# F3-Octo-Brushed-SIDE-USB.net
KiCad netlist of a schematic drawn in EAGLE
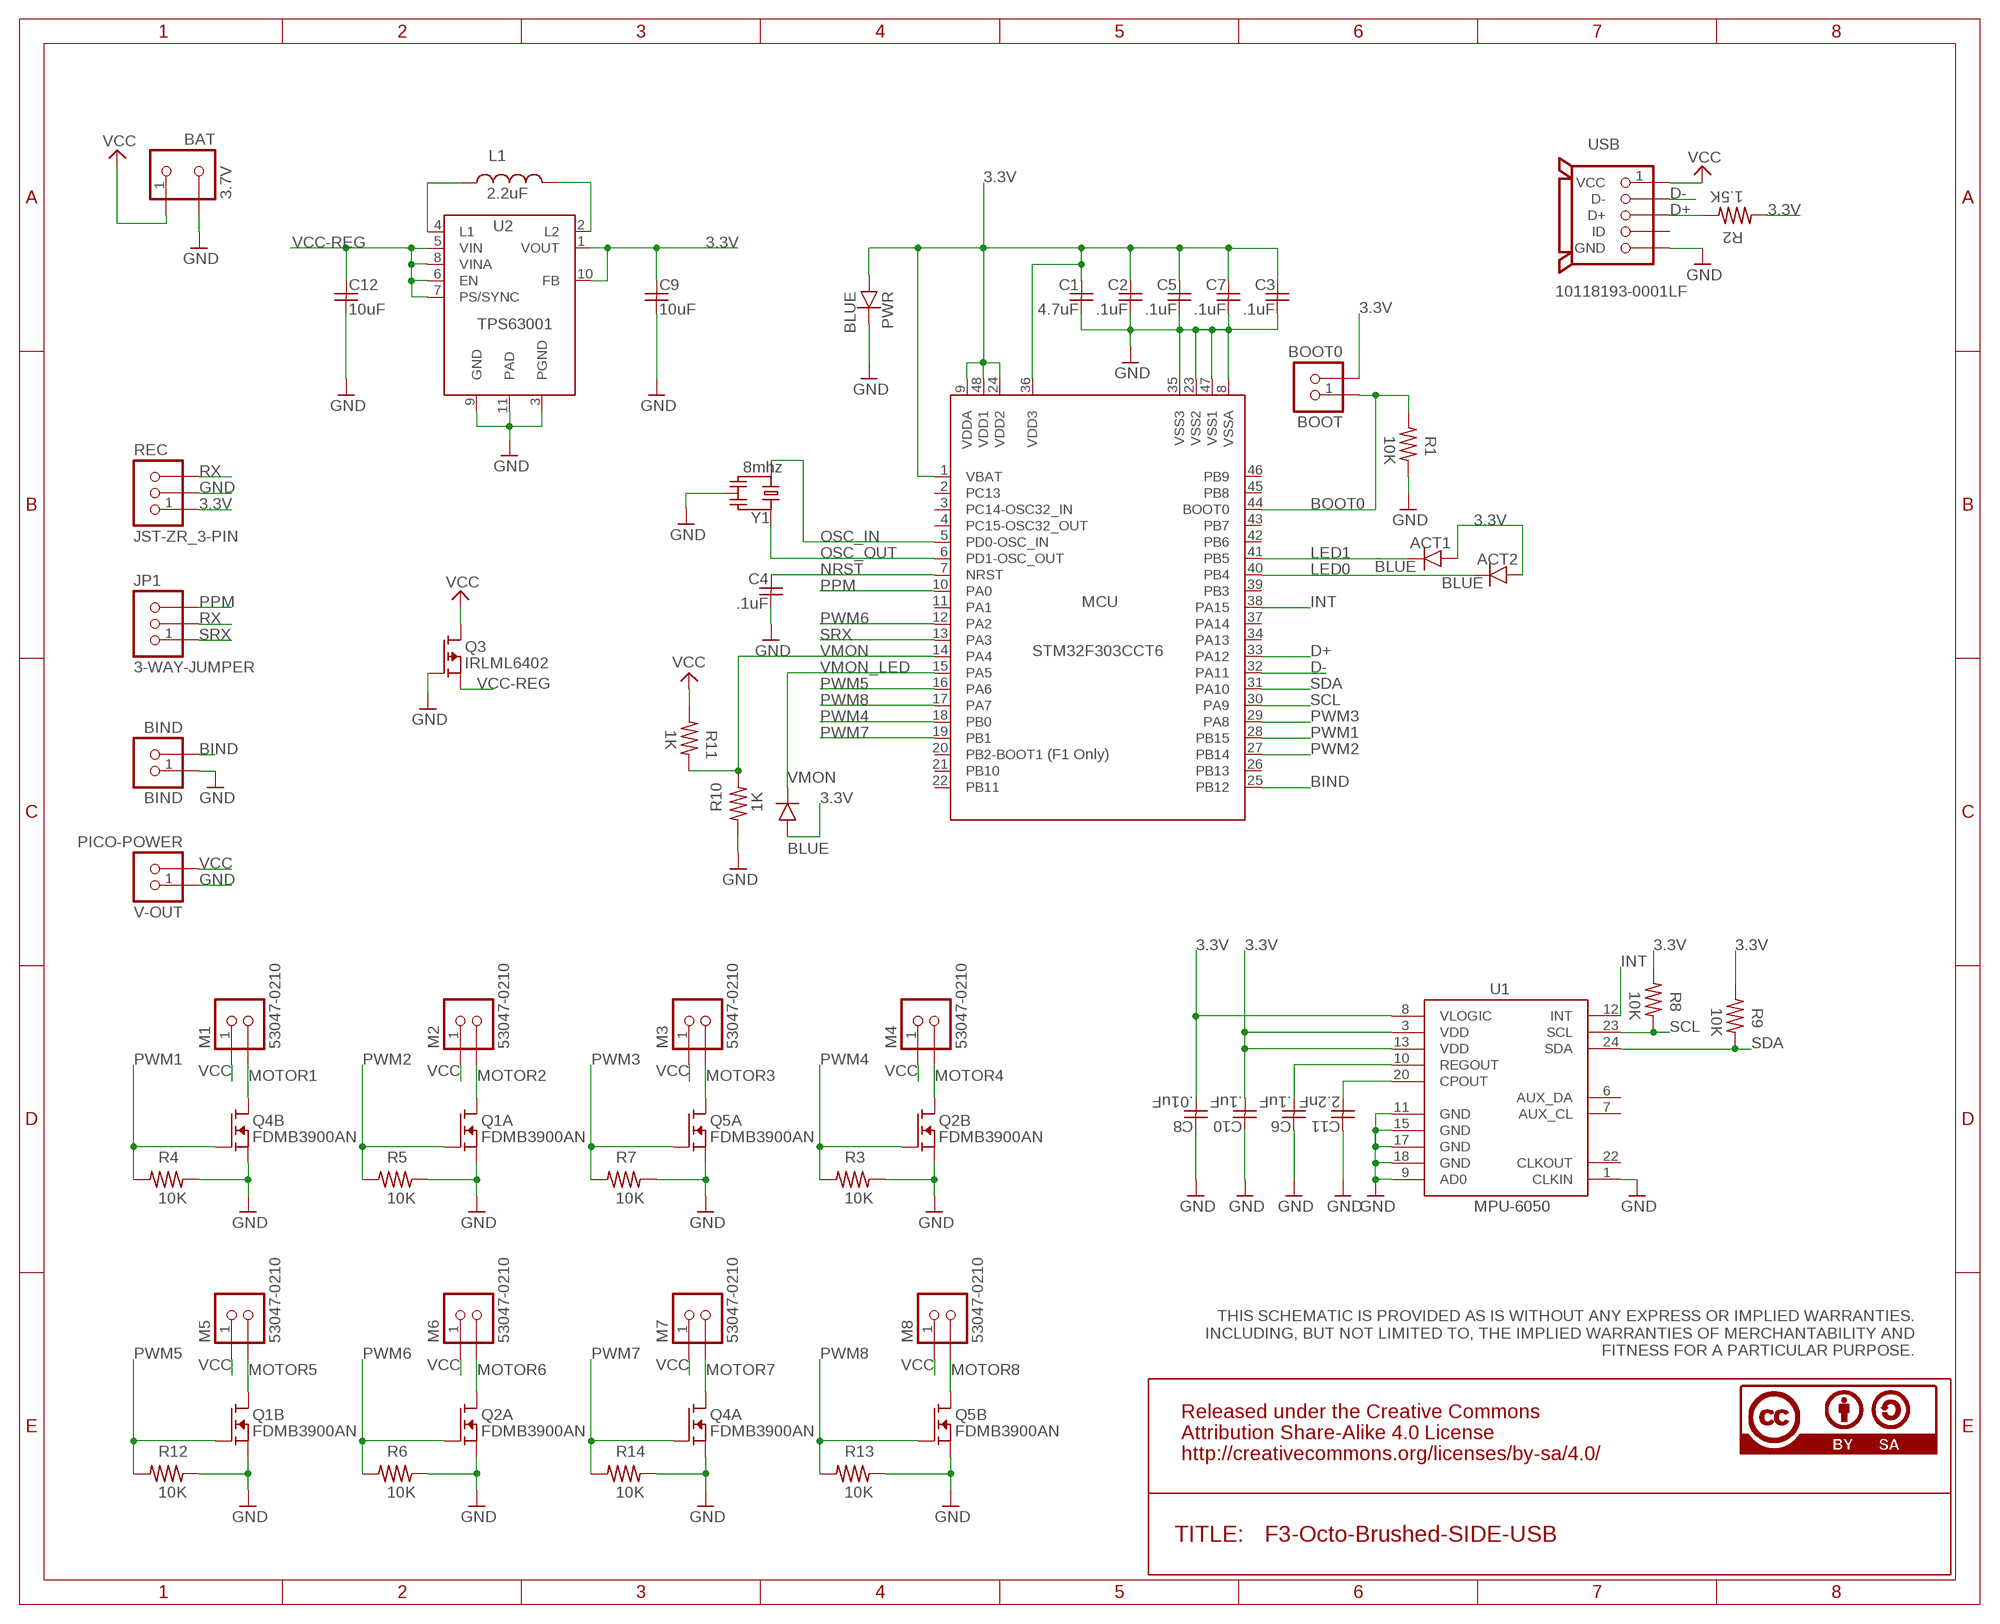
[diagram p0: schematic, sheet 1]

(export (version "E")
  (design (tool "Eeschema 10.0.6"))
  (components
    (comp (ref "ACT1")
      (value "BLUE")
      (footprint "eagle-import:SMD-CHIP-LED-0805")
      (fields (field (name "MF") "Kingbright") (field (name "MPN") "APHCM2012QBC/D-F01"))
      (libsource (lib "eagle-import") (part "SMD-CHIP-LED-0805"))
    )
    (comp (ref "ACT2")
      (value "BLUE")
      (footprint "eagle-import:SMD-CHIP-LED-0805")
      (fields (field (name "MF") "Kingbright") (field (name "MPN") "APHCM2012QBC/D-F01"))
      (libsource (lib "eagle-import") (part "SMD-CHIP-LED-0805"))
    )
    (comp (ref "BAT")
      (value "3.7V")
      (footprint "eagle-import:S2B-PH-K-S")
      (fields (field (name "MF") "JST") (field (name "MPN") "S2B-PH-K-S"))
      (libsource (lib "eagle-import") (part "JST-PH-BAT"))
    )
    (comp (ref "BIND")
      (value "BIND")
      (footprint "eagle-import:B3U-1000P(M)")
      (fields (field (name "MF") "Omron") (field (name "MPN") "B3U-1000P"))
      (libsource (lib "eagle-import") (part "TACTILE-SWITCH"))
    )
    (comp (ref "BOOT")
      (value "BOOT0")
      (footprint "eagle-import:B3U-1000P(M)")
      (fields (field (name "MF") "Omron") (field (name "MPN") "B3U-1000P"))
      (libsource (lib "eagle-import") (part "TACTILE-SWITCH"))
    )
    (comp (ref "C1")
      (value "4.7uF")
      (footprint "eagle-import:MUR-CAP-0603")
      (fields (field (name "MF") "Murata") (field (name "MPN") "GRJ188C70J475KE11D"))
      (libsource (lib "eagle-import") (part "CAPACITOR4.7UF"))
    )
    (comp (ref "C2")
      (value ".1uF")
      (footprint "eagle-import:MUR-CAP-0603")
      (fields (field (name "MF") "Murata") (field (name "MPN") "GRM188R71C104KA01D"))
      (libsource (lib "eagle-import") (part "CAPACITOR.1UF"))
    )
    (comp (ref "C3")
      (value ".1uF")
      (footprint "eagle-import:MUR-CAP-0603")
      (fields (field (name "MF") "Murata") (field (name "MPN") "GRM188R71C104KA01D"))
      (libsource (lib "eagle-import") (part "CAPACITOR.1UF"))
    )
    (comp (ref "C4")
      (value ".1uF")
      (footprint "eagle-import:MUR-CAP-0603")
      (fields (field (name "MF") "Murata") (field (name "MPN") "GRM188R71C104KA01D"))
      (libsource (lib "eagle-import") (part "CAPACITOR.1UF"))
    )
    (comp (ref "C5")
      (value ".1uF")
      (footprint "eagle-import:MUR-CAP-0603")
      (fields (field (name "MF") "Murata") (field (name "MPN") "GRM188R71C104KA01D"))
      (libsource (lib "eagle-import") (part "CAPACITOR.1UF"))
    )
    (comp (ref "C6")
      (value ".1uF")
      (footprint "eagle-import:MUR-CAP-0603")
      (fields (field (name "MF") "Murata") (field (name "MPN") "GRM188R71C104KA01D"))
      (libsource (lib "eagle-import") (part "CAPACITOR.1UF"))
    )
    (comp (ref "C7")
      (value ".1uF")
      (footprint "eagle-import:MUR-CAP-0603")
      (fields (field (name "MF") "Murata") (field (name "MPN") "GRM188R71C104KA01D"))
      (libsource (lib "eagle-import") (part "CAPACITOR.1UF"))
    )
    (comp (ref "C8")
      (value ".01uF")
      (footprint "eagle-import:MUR-CAP-0603")
      (fields (field (name "MF") "Murata") (field (name "MPN") "GRM188R71C103KA01D"))
      (libsource (lib "eagle-import") (part "CAPACITOR.01UF"))
    )
    (comp (ref "C9")
      (value "10uF")
      (footprint "eagle-import:YUDEN-CAP-0805")
      (fields (field (name "MF") "Taiyo Yuden") (field (name "MPN") "JMK212AB7106KG-T"))
      (libsource (lib "eagle-import") (part "CAPACITOR10UF"))
    )
    (comp (ref "C10")
      (value ".1uF")
      (footprint "eagle-import:MUR-CAP-0603")
      (fields (field (name "MF") "Murata") (field (name "MPN") "GRM188R71C104KA01D"))
      (libsource (lib "eagle-import") (part "CAPACITOR.1UF"))
    )
    (comp (ref "C11")
      (value "2.2nF")
      (footprint "eagle-import:MUR-CAP-0603")
      (fields (field (name "MF") "Murata") (field (name "MPN") "GRM188R71C222KA01D"))
      (libsource (lib "eagle-import") (part "CAPACITOR2.2NF"))
    )
    (comp (ref "C12")
      (value "10uF")
      (footprint "eagle-import:YUDEN-CAP-0805")
      (fields (field (name "MF") "Taiyo Yuden") (field (name "MPN") "JMK212AB7106KG-T"))
      (libsource (lib "eagle-import") (part "CAPACITOR10UF"))
    )
    (comp (ref "JP1")
      (value "3-WAY-JUMPER")
      (footprint "eagle-import:3-WAY-JUMPER")
      (libsource (lib "eagle-import") (part "3-WAY-JUMPER"))
    )
    (comp (ref "L1")
      (value "2.2uF")
      (footprint "eagle-import:NR301X")
      (fields (field (name "MF") "Taiyo Yuden") (field (name "MPN") "NR3015T2R2M"))
      (libsource (lib "eagle-import") (part "NR301X"))
    )
    (comp (ref "M1")
      (value "53047-0210")
      (footprint "eagle-import:PICO-53047-02")
      (fields (field (name "MF") "MOLEX"))
      (libsource (lib "eagle-import") (part "PICO-1.25-MOTOR"))
    )
    (comp (ref "M2")
      (value "53047-0210")
      (footprint "eagle-import:PICO-53047-02")
      (fields (field (name "MF") "MOLEX"))
      (libsource (lib "eagle-import") (part "PICO-1.25-MOTOR"))
    )
    (comp (ref "M3")
      (value "53047-0210")
      (footprint "eagle-import:PICO-53047-02")
      (fields (field (name "MF") "MOLEX"))
      (libsource (lib "eagle-import") (part "PICO-1.25-MOTOR"))
    )
    (comp (ref "M4")
      (value "53047-0210")
      (footprint "eagle-import:PICO-53047-02")
      (fields (field (name "MF") "MOLEX"))
      (libsource (lib "eagle-import") (part "PICO-1.25-MOTOR"))
    )
    (comp (ref "M5")
      (value "53047-0210")
      (footprint "eagle-import:PICO-53047-02")
      (fields (field (name "MF") "MOLEX"))
      (libsource (lib "eagle-import") (part "PICO-1.25-MOTOR"))
    )
    (comp (ref "M6")
      (value "53047-0210")
      (footprint "eagle-import:PICO-53047-02")
      (fields (field (name "MF") "MOLEX"))
      (libsource (lib "eagle-import") (part "PICO-1.25-MOTOR"))
    )
    (comp (ref "M7")
      (value "53047-0210")
      (footprint "eagle-import:PICO-53047-02")
      (fields (field (name "MF") "MOLEX"))
      (libsource (lib "eagle-import") (part "PICO-1.25-MOTOR"))
    )
    (comp (ref "M8")
      (value "53047-0210")
      (footprint "eagle-import:PICO-53047-02")
      (fields (field (name "MF") "MOLEX"))
      (libsource (lib "eagle-import") (part "PICO-1.25-MOTOR"))
    )
    (comp (ref "MCU")
      (value "STM32F303CCT6")
      (footprint "eagle-import:LQFP48-7X7")
      (fields (field (name "MF") "ST"))
      (libsource (lib "eagle-import") (part "STM32FX03-F3"))
    )
    (comp (ref "PWR")
      (value "BLUE")
      (footprint "eagle-import:SMD-CHIP-LED-0805")
      (fields (field (name "MF") "Kingbright") (field (name "MPN") "APHCM2012QBC/D-F01"))
      (libsource (lib "eagle-import") (part "SMD-CHIP-LED-0805"))
    )
    (comp (ref "Q1")
      (value "FDMB3900AN")
      (footprint "eagle-import:8-WDFN-DUAL")
      (fields (field (name "MF") "Fairchild"))
      (libsource (lib "eagle-import") (part "FDMB3900AN"))
    )
    (comp (ref "Q2")
      (value "FDMB3900AN")
      (footprint "eagle-import:8-WDFN-DUAL")
      (fields (field (name "MF") "Fairchild"))
      (libsource (lib "eagle-import") (part "FDMB3900AN"))
    )
    (comp (ref "Q3")
      (value "IRLML6402")
      (footprint "eagle-import:SOT-23")
      (fields (field (name "MF") "IR"))
      (libsource (lib "eagle-import") (part "IRLML6402"))
    )
    (comp (ref "Q4")
      (value "FDMB3900AN")
      (footprint "eagle-import:8-WDFN-DUAL")
      (fields (field (name "MF") "Fairchild"))
      (libsource (lib "eagle-import") (part "FDMB3900AN"))
    )
    (comp (ref "Q5")
      (value "FDMB3900AN")
      (footprint "eagle-import:8-WDFN-DUAL")
      (fields (field (name "MF") "Fairchild"))
      (libsource (lib "eagle-import") (part "FDMB3900AN"))
    )
    (comp (ref "R1")
      (value "10K")
      (footprint "eagle-import:VISH-RES-0603")
      (fields (field (name "MF") "Vishay") (field (name "MPN") "CRCW060310K0FKEAHP"))
      (libsource (lib "eagle-import") (part "RESISTOR10K"))
    )
    (comp (ref "R2")
      (value "1.5K")
      (footprint "eagle-import:VISH-RES-0603")
      (fields (field (name "MF") "Vishay") (field (name "MPN") "CRCW06031K50FKEAHP"))
      (libsource (lib "eagle-import") (part "RESISTOR1.5K"))
    )
    (comp (ref "R3")
      (value "10K")
      (footprint "eagle-import:VISH-RES-0603")
      (fields (field (name "MF") "Vishay") (field (name "MPN") "CRCW060310K0FKEAHP"))
      (libsource (lib "eagle-import") (part "RESISTOR10K"))
    )
    (comp (ref "R4")
      (value "10K")
      (footprint "eagle-import:VISH-RES-0603")
      (fields (field (name "MF") "Vishay") (field (name "MPN") "CRCW060310K0FKEAHP"))
      (libsource (lib "eagle-import") (part "RESISTOR10K"))
    )
    (comp (ref "R5")
      (value "10K")
      (footprint "eagle-import:VISH-RES-0603")
      (fields (field (name "MF") "Vishay") (field (name "MPN") "CRCW060310K0FKEAHP"))
      (libsource (lib "eagle-import") (part "RESISTOR10K"))
    )
    (comp (ref "R6")
      (value "10K")
      (footprint "eagle-import:VISH-RES-0603")
      (fields (field (name "MF") "Vishay") (field (name "MPN") "CRCW060310K0FKEAHP"))
      (libsource (lib "eagle-import") (part "RESISTOR10K"))
    )
    (comp (ref "R7")
      (value "10K")
      (footprint "eagle-import:VISH-RES-0603")
      (fields (field (name "MF") "Vishay") (field (name "MPN") "CRCW060310K0FKEAHP"))
      (libsource (lib "eagle-import") (part "RESISTOR10K"))
    )
    (comp (ref "R8")
      (value "10K")
      (footprint "eagle-import:VISH-RES-0603")
      (fields (field (name "MF") "Vishay") (field (name "MPN") "CRCW060310K0FKEAHP"))
      (libsource (lib "eagle-import") (part "RESISTOR10K"))
    )
    (comp (ref "R9")
      (value "10K")
      (footprint "eagle-import:VISH-RES-0603")
      (fields (field (name "MF") "Vishay") (field (name "MPN") "CRCW060310K0FKEAHP"))
      (libsource (lib "eagle-import") (part "RESISTOR10K"))
    )
    (comp (ref "R10")
      (value "1K")
      (footprint "eagle-import:VISH-RES-0603")
      (fields (field (name "MF") "Vishay") (field (name "MPN") "CRCW06031K00FKEAHP"))
      (libsource (lib "eagle-import") (part "RESISTOR1K"))
    )
    (comp (ref "R11")
      (value "1K")
      (footprint "eagle-import:VISH-RES-0603")
      (fields (field (name "MF") "Vishay") (field (name "MPN") "CRCW06031K00FKEAHP"))
      (libsource (lib "eagle-import") (part "RESISTOR1K"))
    )
    (comp (ref "R12")
      (value "10K")
      (footprint "eagle-import:VISH-RES-0603")
      (fields (field (name "MF") "Vishay") (field (name "MPN") "CRCW060310K0FKEAHP"))
      (libsource (lib "eagle-import") (part "RESISTOR10K"))
    )
    (comp (ref "R13")
      (value "10K")
      (footprint "eagle-import:VISH-RES-0603")
      (fields (field (name "MF") "Vishay") (field (name "MPN") "CRCW060310K0FKEAHP"))
      (libsource (lib "eagle-import") (part "RESISTOR10K"))
    )
    (comp (ref "R14")
      (value "10K")
      (footprint "eagle-import:VISH-RES-0603")
      (fields (field (name "MF") "Vishay") (field (name "MPN") "CRCW060310K0FKEAHP"))
      (libsource (lib "eagle-import") (part "RESISTOR10K"))
    )
    (comp (ref "REC")
      (value "JST-ZR_3-PIN")
      (footprint "eagle-import:S3B-ZR")
      (fields (field (name "MF") "JST") (field (name "MPN") "S3B-ZR"))
      (libsource (lib "eagle-import") (part "JST-ZR_3-PIN"))
    )
    (comp (ref "U1")
      (value "MPU-6050")
      (footprint "eagle-import:QFN24-4X4")
      (fields (field (name "MF") "Invensense"))
      (libsource (lib "eagle-import") (part "MPU-6050"))
    )
    (comp (ref "U2")
      (value "TPS63001")
      (footprint "eagle-import:VSON-N10")
      (fields (field (name "MF") "TI") (field (name "MPN") "TPS63001DRCR"))
      (libsource (lib "eagle-import") (part "TPS630XX-TPS63001"))
    )
    (comp (ref "USB")
      (value "10118193-0001LF")
      (footprint "eagle-import:10118193-0001LF")
      (fields (field (name "MF") "FCI"))
      (libsource (lib "eagle-import") (part "USB-MICRO-B-FCI"))
    )
    (comp (ref "V-OUT")
      (value "PICO-POWER")
      (footprint "eagle-import:PICO_1.25_.5MM")
      (fields (field (name "MF") "Molex") (field (name "MPN") "53047-0210"))
      (libsource (lib "eagle-import") (part "PICO-POWER"))
    )
    (comp (ref "VMON")
      (value "BLUE")
      (footprint "eagle-import:SMD-CHIP-LED-0805")
      (fields (field (name "MF") "Kingbright") (field (name "MPN") "APHCM2012QBC/D-F01"))
      (libsource (lib "eagle-import") (part "SMD-CHIP-LED-0805"))
    )
    (comp (ref "Y1")
      (value "8mhz")
      (footprint "eagle-import:RESONATOR_8")
      (fields (field (name "MF") "Murata") (field (name "MPN") "CSTCE8M00G55-R0"))
      (libsource (lib "eagle-import") (part "RESONATOR8MHZ"))
    )
  )
  (nets
    (net (code "1") (name "/3.3V") (class "Default")
      (node (ref "ACT1") (pin "A") (pinfunction "A_A") (pintype "passive"))
      (node (ref "ACT2") (pin "A") (pinfunction "A_A") (pintype "passive"))
      (node (ref "BOOT") (pin "2") (pinfunction "2_2") (pintype "passive"))
      (node (ref "C1") (pin "1") (pinfunction "1_1") (pintype "passive"))
      (node (ref "C10") (pin "2") (pinfunction "2_2") (pintype "passive"))
      (node (ref "C2") (pin "1") (pinfunction "1_1") (pintype "passive"))
      (node (ref "C3") (pin "1") (pinfunction "1_1") (pintype "passive"))
      (node (ref "C5") (pin "1") (pinfunction "1_1") (pintype "passive"))
      (node (ref "C7") (pin "1") (pinfunction "1_1") (pintype "passive"))
      (node (ref "C8") (pin "2") (pinfunction "2_2") (pintype "passive"))
      (node (ref "C9") (pin "1") (pinfunction "1_1") (pintype "passive"))
      (node (ref "MCU") (pin "1") (pinfunction "VBAT_1") (pintype "bidirectional"))
      (node (ref "MCU") (pin "24") (pinfunction "VDD2_24") (pintype "bidirectional"))
      (node (ref "MCU") (pin "36") (pinfunction "VDD3_36") (pintype "bidirectional"))
      (node (ref "MCU") (pin "48") (pinfunction "VDD1_48") (pintype "bidirectional"))
      (node (ref "MCU") (pin "9") (pinfunction "VDDA_9") (pintype "bidirectional"))
      (node (ref "PWR") (pin "A") (pinfunction "A_A") (pintype "passive"))
      (node (ref "R2") (pin "2") (pinfunction "2_2") (pintype "passive"))
      (node (ref "R8") (pin "2") (pinfunction "2_2") (pintype "passive"))
      (node (ref "R9") (pin "2") (pinfunction "2_2") (pintype "passive"))
      (node (ref "REC") (pin "1") (pinfunction "1_1") (pintype "bidirectional"))
      (node (ref "U1") (pin "13") (pinfunction "VDD_13") (pintype "bidirectional"))
      (node (ref "U1") (pin "3") (pinfunction "VDD_3") (pintype "bidirectional"))
      (node (ref "U1") (pin "8") (pinfunction "VLOGIC_8") (pintype "bidirectional"))
      (node (ref "U2") (pin "1") (pinfunction "VOUT_1") (pintype "bidirectional"))
      (node (ref "U2") (pin "10") (pinfunction "FB_10") (pintype "bidirectional"))
      (node (ref "VMON") (pin "A") (pinfunction "A_A") (pintype "passive"))
    )
    (net (code "2") (name "/BIND") (class "Default")
      (node (ref "BIND") (pin "2") (pinfunction "2_2") (pintype "passive"))
      (node (ref "MCU") (pin "25") (pinfunction "PB12_25") (pintype "bidirectional"))
    )
    (net (code "3") (name "/BOOT0") (class "Default")
      (node (ref "BOOT") (pin "1") (pinfunction "1_1") (pintype "passive"))
      (node (ref "MCU") (pin "44") (pinfunction "BOOT0_44") (pintype "bidirectional"))
      (node (ref "R1") (pin "2") (pinfunction "2_2") (pintype "passive"))
    )
    (net (code "4") (name "/D+") (class "Default")
      (node (ref "MCU") (pin "33") (pinfunction "PA12_33") (pintype "bidirectional"))
      (node (ref "R2") (pin "1") (pinfunction "1_1") (pintype "passive"))
      (node (ref "USB") (pin "3") (pinfunction "D+_3") (pintype "passive"))
    )
    (net (code "5") (name "/D-") (class "Default")
      (node (ref "MCU") (pin "32") (pinfunction "PA11_32") (pintype "bidirectional"))
      (node (ref "USB") (pin "2") (pinfunction "D-_2") (pintype "passive"))
    )
    (net (code "6") (name "/INT") (class "Default")
      (node (ref "MCU") (pin "38") (pinfunction "PA15_38") (pintype "bidirectional"))
      (node (ref "U1") (pin "12") (pinfunction "INT_12") (pintype "bidirectional"))
    )
    (net (code "7") (name "/LED0") (class "Default")
      (node (ref "ACT2") (pin "C") (pinfunction "C_C") (pintype "passive"))
      (node (ref "MCU") (pin "40") (pinfunction "PB4_40") (pintype "bidirectional"))
    )
    (net (code "8") (name "/LED1") (class "Default")
      (node (ref "ACT1") (pin "C") (pinfunction "C_C") (pintype "passive"))
      (node (ref "MCU") (pin "41") (pinfunction "PB5_41") (pintype "bidirectional"))
    )
    (net (code "9") (name "/MOTOR1") (class "Default")
      (node (ref "M1") (pin "2") (pinfunction "2_2") (pintype "passive"))
      (node (ref "Q4") (pin "5+6") (pinfunction "D_5+6") (pintype "bidirectional"))
    )
    (net (code "10") (name "/MOTOR2") (class "Default")
      (node (ref "M2") (pin "2") (pinfunction "2_2") (pintype "passive"))
      (node (ref "Q1") (pin "7+8") (pinfunction "D_7+8") (pintype "bidirectional"))
    )
    (net (code "11") (name "/MOTOR3") (class "Default")
      (node (ref "M3") (pin "2") (pinfunction "2_2") (pintype "passive"))
      (node (ref "Q5") (pin "7+8") (pinfunction "D_7+8") (pintype "bidirectional"))
    )
    (net (code "12") (name "/MOTOR4") (class "Default")
      (node (ref "M4") (pin "2") (pinfunction "2_2") (pintype "passive"))
      (node (ref "Q2") (pin "5+6") (pinfunction "D_5+6") (pintype "bidirectional"))
    )
    (net (code "13") (name "/MOTOR5") (class "Default")
      (node (ref "M5") (pin "2") (pinfunction "2_2") (pintype "passive"))
      (node (ref "Q1") (pin "5+6") (pinfunction "D_5+6") (pintype "bidirectional"))
    )
    (net (code "14") (name "/MOTOR6") (class "Default")
      (node (ref "M6") (pin "2") (pinfunction "2_2") (pintype "passive"))
      (node (ref "Q2") (pin "7+8") (pinfunction "D_7+8") (pintype "bidirectional"))
    )
    (net (code "15") (name "/MOTOR7") (class "Default")
      (node (ref "M7") (pin "2") (pinfunction "2_2") (pintype "passive"))
      (node (ref "Q4") (pin "7+8") (pinfunction "D_7+8") (pintype "bidirectional"))
    )
    (net (code "16") (name "/MOTOR8") (class "Default")
      (node (ref "M8") (pin "2") (pinfunction "2_2") (pintype "passive"))
      (node (ref "Q5") (pin "5+6") (pinfunction "D_5+6") (pintype "bidirectional"))
    )
    (net (code "17") (name "/NRST") (class "Default")
      (node (ref "C4") (pin "1") (pinfunction "1_1") (pintype "passive"))
      (node (ref "MCU") (pin "7") (pinfunction "NRST_7") (pintype "bidirectional"))
    )
    (net (code "18") (name "/OSC_IN") (class "Default")
      (node (ref "MCU") (pin "5") (pinfunction "PD0-OSC_IN_5") (pintype "bidirectional"))
      (node (ref "Y1") (pin "3") (pinfunction "3_3") (pintype "passive"))
    )
    (net (code "19") (name "/OSC_OUT") (class "Default")
      (node (ref "MCU") (pin "6") (pinfunction "PD1-OSC_OUT_6") (pintype "bidirectional"))
      (node (ref "Y1") (pin "1") (pinfunction "1_1") (pintype "passive"))
    )
    (net (code "20") (name "/PPM") (class "Default")
      (node (ref "JP1") (pin "3") (pinfunction "3_3") (pintype "bidirectional"))
      (node (ref "MCU") (pin "10") (pinfunction "PA0_10") (pintype "bidirectional"))
    )
    (net (code "21") (name "/PWM1") (class "Default")
      (node (ref "MCU") (pin "28") (pinfunction "PB15_28") (pintype "bidirectional"))
      (node (ref "Q4") (pin "4@G2") (pinfunction "G_4@G2") (pintype "bidirectional"))
      (node (ref "R4") (pin "2") (pinfunction "2_2") (pintype "passive"))
    )
    (net (code "22") (name "/PWM2") (class "Default")
      (node (ref "MCU") (pin "27") (pinfunction "PB14_27") (pintype "bidirectional"))
      (node (ref "Q1") (pin "2@G1") (pinfunction "G_2@G1") (pintype "bidirectional"))
      (node (ref "R5") (pin "2") (pinfunction "2_2") (pintype "passive"))
    )
    (net (code "23") (name "/PWM3") (class "Default")
      (node (ref "MCU") (pin "29") (pinfunction "PA8_29") (pintype "bidirectional"))
      (node (ref "Q5") (pin "2@G1") (pinfunction "G_2@G1") (pintype "bidirectional"))
      (node (ref "R7") (pin "2") (pinfunction "2_2") (pintype "passive"))
    )
    (net (code "24") (name "/PWM4") (class "Default")
      (node (ref "MCU") (pin "18") (pinfunction "PB0_18") (pintype "bidirectional"))
      (node (ref "Q2") (pin "4@G2") (pinfunction "G_4@G2") (pintype "bidirectional"))
      (node (ref "R3") (pin "2") (pinfunction "2_2") (pintype "passive"))
    )
    (net (code "25") (name "/PWM5") (class "Default")
      (node (ref "MCU") (pin "16") (pinfunction "PA6_16") (pintype "bidirectional"))
      (node (ref "Q1") (pin "4@G2") (pinfunction "G_4@G2") (pintype "bidirectional"))
      (node (ref "R12") (pin "2") (pinfunction "2_2") (pintype "passive"))
    )
    (net (code "26") (name "/PWM6") (class "Default")
      (node (ref "MCU") (pin "12") (pinfunction "PA2_12") (pintype "bidirectional"))
      (node (ref "Q2") (pin "2@G1") (pinfunction "G_2@G1") (pintype "bidirectional"))
      (node (ref "R6") (pin "2") (pinfunction "2_2") (pintype "passive"))
    )
    (net (code "27") (name "/PWM7") (class "Default")
      (node (ref "MCU") (pin "19") (pinfunction "PB1_19") (pintype "bidirectional"))
      (node (ref "Q4") (pin "2@G1") (pinfunction "G_2@G1") (pintype "bidirectional"))
      (node (ref "R14") (pin "2") (pinfunction "2_2") (pintype "passive"))
    )
    (net (code "28") (name "/PWM8") (class "Default")
      (node (ref "MCU") (pin "17") (pinfunction "PA7_17") (pintype "bidirectional"))
      (node (ref "Q5") (pin "4@G2") (pinfunction "G_4@G2") (pintype "bidirectional"))
      (node (ref "R13") (pin "2") (pinfunction "2_2") (pintype "passive"))
    )
    (net (code "29") (name "/RX") (class "Default")
      (node (ref "JP1") (pin "2") (pinfunction "2_2") (pintype "bidirectional"))
      (node (ref "REC") (pin "3") (pinfunction "3_3") (pintype "bidirectional"))
    )
    (net (code "30") (name "/SCL") (class "Default")
      (node (ref "MCU") (pin "30") (pinfunction "PA9_30") (pintype "bidirectional"))
      (node (ref "R8") (pin "1") (pinfunction "1_1") (pintype "passive"))
      (node (ref "U1") (pin "23") (pinfunction "SCL_23") (pintype "bidirectional"))
    )
    (net (code "31") (name "/SDA") (class "Default")
      (node (ref "MCU") (pin "31") (pinfunction "PA10_31") (pintype "bidirectional"))
      (node (ref "R9") (pin "1") (pinfunction "1_1") (pintype "passive"))
      (node (ref "U1") (pin "24") (pinfunction "SDA_24") (pintype "bidirectional"))
    )
    (net (code "32") (name "/SRX") (class "Default")
      (node (ref "JP1") (pin "1") (pinfunction "1_1") (pintype "bidirectional"))
      (node (ref "MCU") (pin "13") (pinfunction "PA3_13") (pintype "bidirectional"))
    )
    (net (code "33") (name "/VCC-REG") (class "Default")
      (node (ref "C12") (pin "1") (pinfunction "1_1") (pintype "passive"))
      (node (ref "Q3") (pin "2") (pinfunction "S_2") (pintype "bidirectional"))
      (node (ref "U2") (pin "5") (pinfunction "VIN_5") (pintype "bidirectional"))
      (node (ref "U2") (pin "6") (pinfunction "EN_6") (pintype "bidirectional"))
      (node (ref "U2") (pin "7") (pinfunction "PS/SYNC_7") (pintype "bidirectional"))
      (node (ref "U2") (pin "8") (pinfunction "VINA_8") (pintype "bidirectional"))
    )
    (net (code "34") (name "/VMON") (class "Default")
      (node (ref "MCU") (pin "14") (pinfunction "PA4_14") (pintype "bidirectional"))
      (node (ref "R10") (pin "1") (pinfunction "1_1") (pintype "passive"))
      (node (ref "R11") (pin "1") (pinfunction "1_1") (pintype "passive"))
    )
    (net (code "35") (name "/VMON_LED") (class "Default")
      (node (ref "MCU") (pin "15") (pinfunction "PA5_15") (pintype "bidirectional"))
      (node (ref "VMON") (pin "C") (pinfunction "C_C") (pintype "passive"))
    )
    (net (code "36") (name "GND") (class "Default")
      (node (ref "BAT") (pin "2") (pinfunction "2_2") (pintype "bidirectional"))
      (node (ref "BIND") (pin "1") (pinfunction "1_1") (pintype "passive"))
      (node (ref "C1") (pin "2") (pinfunction "2_2") (pintype "passive"))
      (node (ref "C10") (pin "1") (pinfunction "1_1") (pintype "passive"))
      (node (ref "C11") (pin "1") (pinfunction "1_1") (pintype "passive"))
      (node (ref "C12") (pin "2") (pinfunction "2_2") (pintype "passive"))
      (node (ref "C2") (pin "2") (pinfunction "2_2") (pintype "passive"))
      (node (ref "C3") (pin "2") (pinfunction "2_2") (pintype "passive"))
      (node (ref "C4") (pin "2") (pinfunction "2_2") (pintype "passive"))
      (node (ref "C5") (pin "2") (pinfunction "2_2") (pintype "passive"))
      (node (ref "C6") (pin "1") (pinfunction "1_1") (pintype "passive"))
      (node (ref "C7") (pin "2") (pinfunction "2_2") (pintype "passive"))
      (node (ref "C8") (pin "1") (pinfunction "1_1") (pintype "passive"))
      (node (ref "C9") (pin "2") (pinfunction "2_2") (pintype "passive"))
      (node (ref "MCU") (pin "23") (pinfunction "VSS2_23") (pintype "bidirectional"))
      (node (ref "MCU") (pin "35") (pinfunction "VSS3_35") (pintype "bidirectional"))
      (node (ref "MCU") (pin "47") (pinfunction "VSS1_47") (pintype "bidirectional"))
      (node (ref "MCU") (pin "8") (pinfunction "VSSA_8") (pintype "bidirectional"))
      (node (ref "PWR") (pin "C") (pinfunction "C_C") (pintype "passive"))
      (node (ref "Q1") (pin "1@S1") (pinfunction "S_1@S1") (pintype "bidirectional"))
      (node (ref "Q1") (pin "3@S1") (pinfunction "S_3@S1") (pintype "bidirectional"))
      (node (ref "Q2") (pin "1@S1") (pinfunction "S_1@S1") (pintype "bidirectional"))
      (node (ref "Q2") (pin "3@S1") (pinfunction "S_3@S1") (pintype "bidirectional"))
      (node (ref "Q3") (pin "1") (pinfunction "G_1") (pintype "bidirectional"))
      (node (ref "Q4") (pin "1@S1") (pinfunction "S_1@S1") (pintype "bidirectional"))
      (node (ref "Q4") (pin "3@S1") (pinfunction "S_3@S1") (pintype "bidirectional"))
      (node (ref "Q5") (pin "1@S1") (pinfunction "S_1@S1") (pintype "bidirectional"))
      (node (ref "Q5") (pin "3@S1") (pinfunction "S_3@S1") (pintype "bidirectional"))
      (node (ref "R1") (pin "1") (pinfunction "1_1") (pintype "passive"))
      (node (ref "R10") (pin "2") (pinfunction "2_2") (pintype "passive"))
      (node (ref "R12") (pin "1") (pinfunction "1_1") (pintype "passive"))
      (node (ref "R13") (pin "1") (pinfunction "1_1") (pintype "passive"))
      (node (ref "R14") (pin "1") (pinfunction "1_1") (pintype "passive"))
      (node (ref "R3") (pin "1") (pinfunction "1_1") (pintype "passive"))
      (node (ref "R4") (pin "1") (pinfunction "1_1") (pintype "passive"))
      (node (ref "R5") (pin "1") (pinfunction "1_1") (pintype "passive"))
      (node (ref "R6") (pin "1") (pinfunction "1_1") (pintype "passive"))
      (node (ref "R7") (pin "1") (pinfunction "1_1") (pintype "passive"))
      (node (ref "REC") (pin "2") (pinfunction "2_2") (pintype "bidirectional"))
      (node (ref "U1") (pin "1") (pinfunction "CLKIN_1") (pintype "bidirectional"))
      (node (ref "U1") (pin "11") (pinfunction "GND_11") (pintype "bidirectional"))
      (node (ref "U1") (pin "15") (pinfunction "GND_15") (pintype "bidirectional"))
      (node (ref "U1") (pin "17") (pinfunction "GND_17") (pintype "bidirectional"))
      (node (ref "U1") (pin "18") (pinfunction "GND_18") (pintype "bidirectional"))
      (node (ref "U1") (pin "9") (pinfunction "AD0_9") (pintype "bidirectional"))
      (node (ref "U2") (pin "11") (pinfunction "PAD_11") (pintype "bidirectional"))
      (node (ref "U2") (pin "3") (pinfunction "PGND_3") (pintype "bidirectional"))
      (node (ref "U2") (pin "9") (pinfunction "GND_9") (pintype "bidirectional"))
      (node (ref "USB") (pin "5") (pinfunction "GND_5") (pintype "passive"))
      (node (ref "USB") (pin "GND") (pinfunction "GND_GND") (pintype "passive"))
      (node (ref "USB") (pin "GND2") (pinfunction "GND_GND2") (pintype "passive"))
      (node (ref "USB") (pin "HOLE1") (pinfunction "GND_HOLE1") (pintype "passive"))
      (node (ref "USB") (pin "HOLE2") (pinfunction "GND_HOLE2") (pintype "passive"))
      (node (ref "V-OUT") (pin "1") (pinfunction "1_1") (pintype "passive"))
      (node (ref "Y1") (pin "2") (pinfunction "2_2") (pintype "passive"))
    )
    (net (code "37") (name "Net-(U1-CPOUT)") (class "Default")
      (node (ref "C11") (pin "2") (pinfunction "2_2") (pintype "passive"))
      (node (ref "U1") (pin "20") (pinfunction "CPOUT_20") (pintype "bidirectional"))
    )
    (net (code "38") (name "Net-(U1-REGOUT)") (class "Default")
      (node (ref "C6") (pin "2") (pinfunction "2_2") (pintype "passive"))
      (node (ref "U1") (pin "10") (pinfunction "REGOUT_10") (pintype "bidirectional"))
    )
    (net (code "39") (name "Net-(U2-L1)") (class "Default")
      (node (ref "L1") (pin "1") (pinfunction "1_1") (pintype "passive"))
      (node (ref "U2") (pin "4") (pinfunction "L1_4") (pintype "bidirectional"))
    )
    (net (code "40") (name "Net-(U2-L2)") (class "Default")
      (node (ref "L1") (pin "2") (pinfunction "2_2") (pintype "passive"))
      (node (ref "U2") (pin "2") (pinfunction "L2_2") (pintype "bidirectional"))
    )
    (net (code "41") (name "VCC") (class "Default")
      (node (ref "BAT") (pin "1") (pinfunction "1_1") (pintype "bidirectional"))
      (node (ref "M1") (pin "1") (pinfunction "1_1") (pintype "passive"))
      (node (ref "M2") (pin "1") (pinfunction "1_1") (pintype "passive"))
      (node (ref "M3") (pin "1") (pinfunction "1_1") (pintype "passive"))
      (node (ref "M4") (pin "1") (pinfunction "1_1") (pintype "passive"))
      (node (ref "M5") (pin "1") (pinfunction "1_1") (pintype "passive"))
      (node (ref "M6") (pin "1") (pinfunction "1_1") (pintype "passive"))
      (node (ref "M7") (pin "1") (pinfunction "1_1") (pintype "passive"))
      (node (ref "M8") (pin "1") (pinfunction "1_1") (pintype "passive"))
      (node (ref "Q3") (pin "3") (pinfunction "D_3") (pintype "bidirectional"))
      (node (ref "R11") (pin "2") (pinfunction "2_2") (pintype "passive"))
      (node (ref "USB") (pin "1") (pinfunction "VCC_1") (pintype "passive"))
      (node (ref "V-OUT") (pin "2") (pinfunction "2_2") (pintype "passive"))
    )
    (net (code "42") (name "unconnected-(MCU-PA1-Pad11)") (class "Default")
      (node (ref "MCU") (pin "11") (pinfunction "PA1_11") (pintype "bidirectional"))
    )
    (net (code "43") (name "unconnected-(MCU-PA13-Pad34)") (class "Default")
      (node (ref "MCU") (pin "34") (pinfunction "PA13_34") (pintype "bidirectional"))
    )
    (net (code "44") (name "unconnected-(MCU-PA14-Pad37)") (class "Default")
      (node (ref "MCU") (pin "37") (pinfunction "PA14_37") (pintype "bidirectional"))
    )
    (net (code "45") (name "unconnected-(MCU-PB2-BOOT1-Pad20)") (class "Default")
      (node (ref "MCU") (pin "20") (pinfunction "PB2-BOOT1_20") (pintype "bidirectional"))
    )
    (net (code "46") (name "unconnected-(MCU-PB3-Pad39)") (class "Default")
      (node (ref "MCU") (pin "39") (pinfunction "PB3_39") (pintype "bidirectional"))
    )
    (net (code "47") (name "unconnected-(MCU-PB6-Pad42)") (class "Default")
      (node (ref "MCU") (pin "42") (pinfunction "PB6_42") (pintype "bidirectional"))
    )
    (net (code "48") (name "unconnected-(MCU-PB7-Pad43)") (class "Default")
      (node (ref "MCU") (pin "43") (pinfunction "PB7_43") (pintype "bidirectional"))
    )
    (net (code "49") (name "unconnected-(MCU-PB8-Pad45)") (class "Default")
      (node (ref "MCU") (pin "45") (pinfunction "PB8_45") (pintype "bidirectional"))
    )
    (net (code "50") (name "unconnected-(MCU-PB9-Pad46)") (class "Default")
      (node (ref "MCU") (pin "46") (pinfunction "PB9_46") (pintype "bidirectional"))
    )
    (net (code "51") (name "unconnected-(MCU-PB10-Pad21)") (class "Default")
      (node (ref "MCU") (pin "21") (pinfunction "PB10_21") (pintype "bidirectional"))
    )
    (net (code "52") (name "unconnected-(MCU-PB11-Pad22)") (class "Default")
      (node (ref "MCU") (pin "22") (pinfunction "PB11_22") (pintype "bidirectional"))
    )
    (net (code "53") (name "unconnected-(MCU-PB13-Pad26)") (class "Default")
      (node (ref "MCU") (pin "26") (pinfunction "PB13_26") (pintype "bidirectional"))
    )
    (net (code "54") (name "unconnected-(MCU-PC13-Pad2)") (class "Default")
      (node (ref "MCU") (pin "2") (pinfunction "PC13_2") (pintype "bidirectional"))
    )
    (net (code "55") (name "unconnected-(MCU-PC14-OSC32_IN-Pad3)") (class "Default")
      (node (ref "MCU") (pin "3") (pinfunction "PC14-OSC32_IN_3") (pintype "bidirectional"))
    )
    (net (code "56") (name "unconnected-(MCU-PC15-OSC32_OUT-Pad4)") (class "Default")
      (node (ref "MCU") (pin "4") (pinfunction "PC15-OSC32_OUT_4") (pintype "bidirectional"))
    )
    (net (code "57") (name "unconnected-(U1-AUX_CL-Pad7)") (class "Default")
      (node (ref "U1") (pin "7") (pinfunction "AUX_CL_7") (pintype "bidirectional"))
    )
    (net (code "58") (name "unconnected-(U1-AUX_DA-Pad6)") (class "Default")
      (node (ref "U1") (pin "6") (pinfunction "AUX_DA_6") (pintype "bidirectional"))
    )
    (net (code "59") (name "unconnected-(U1-CLKOUT-Pad22)") (class "Default")
      (node (ref "U1") (pin "22") (pinfunction "CLKOUT_22") (pintype "bidirectional"))
    )
    (net (code "60") (name "unconnected-(USB-ID-Pad4)") (class "Default")
      (node (ref "USB") (pin "4") (pinfunction "ID_4") (pintype "passive"))
    )
  )
)
